# AetherMesh_Test_Fixture_Mezz_V1_0.net
KiCad netlist of a schematic drawn in EAGLE
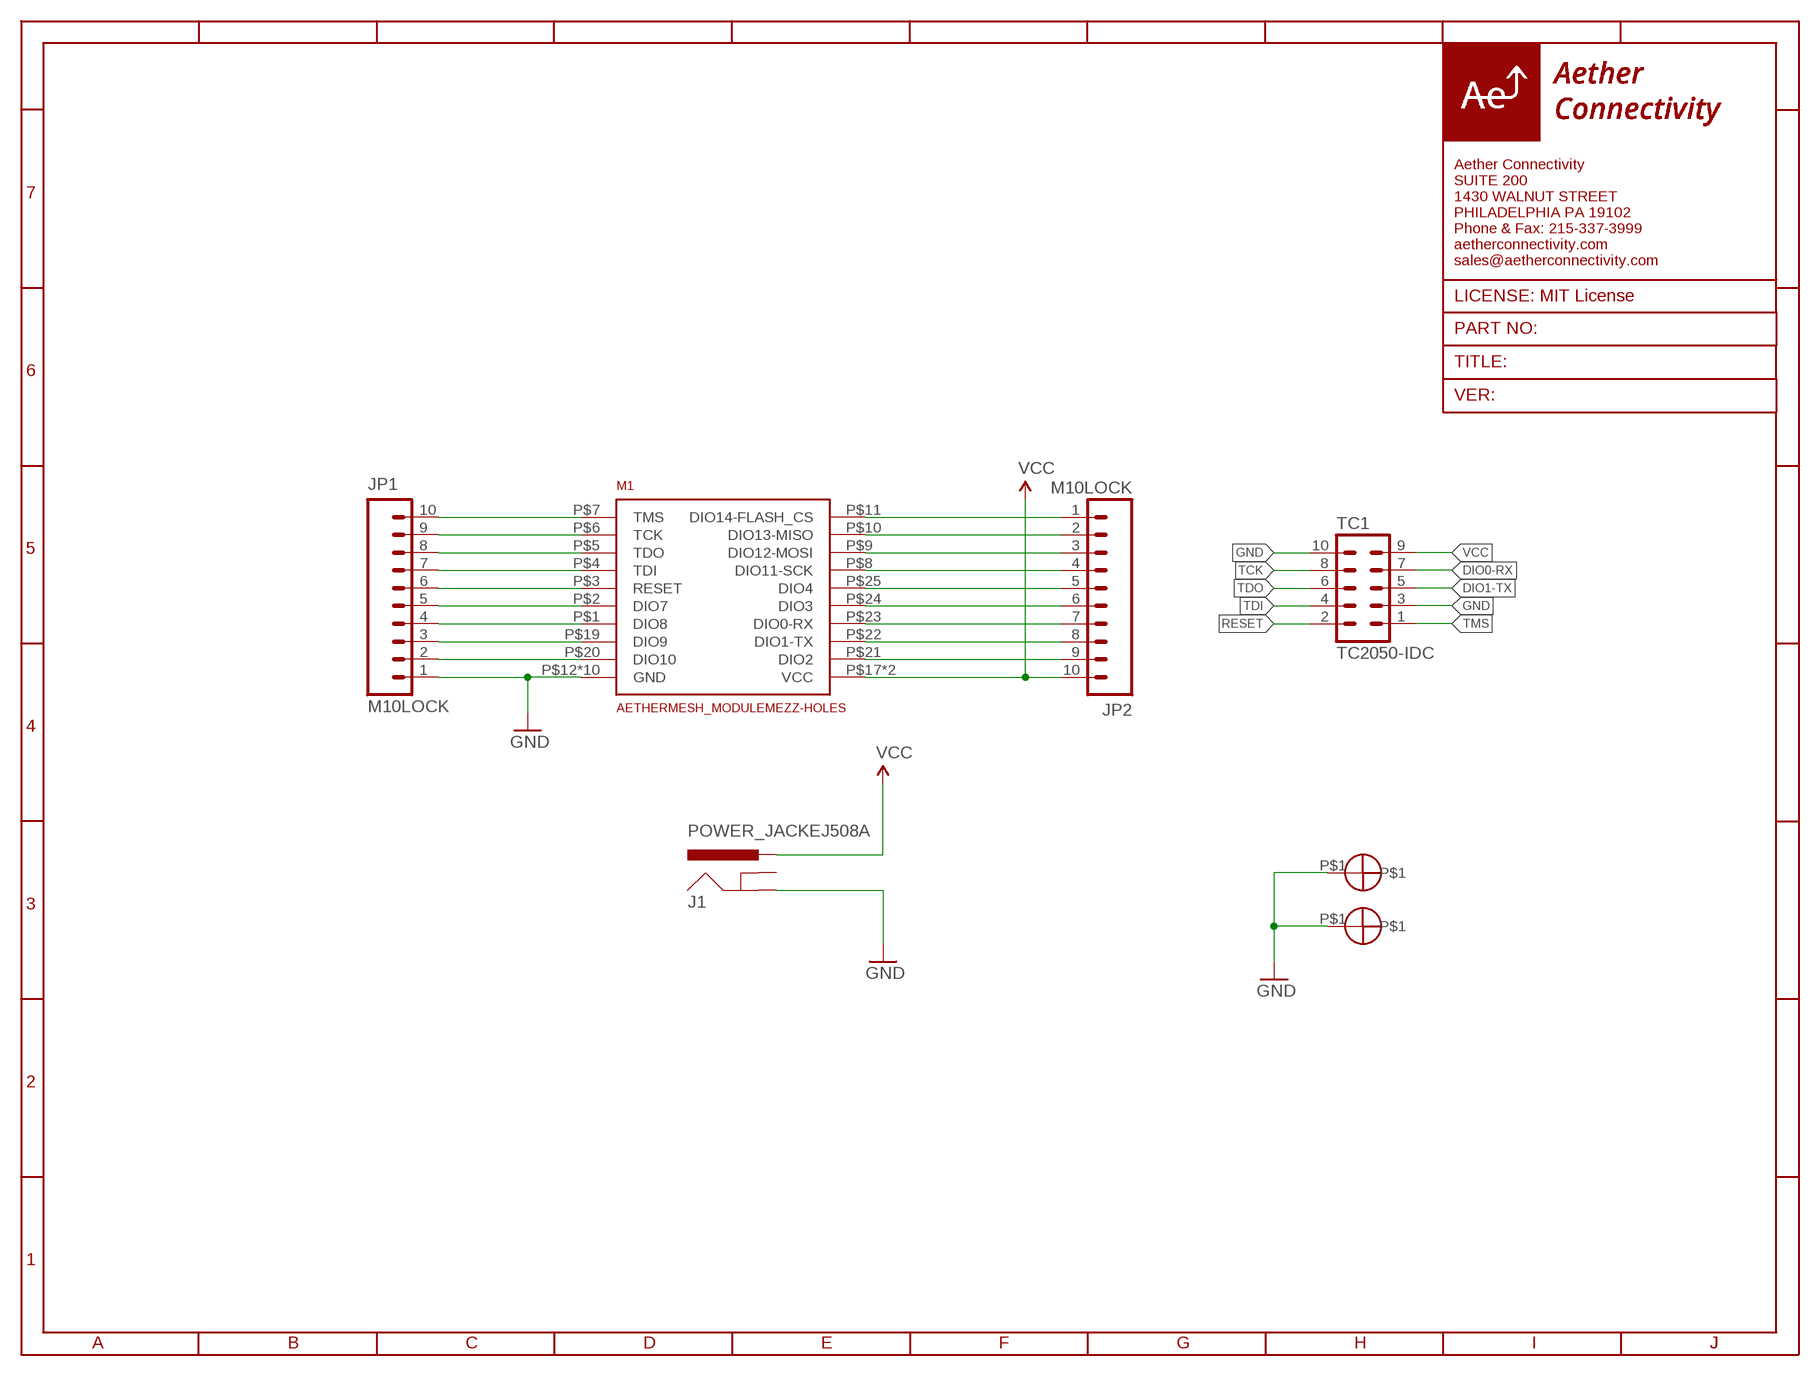
[diagram p0: schematic, sheet 1]

(export (version "E")
  (design (tool "Eeschema 10.0.6"))
  (components
    (comp (ref "J1")
      (value "POWER_JACKEJ508A")
      (footprint "eagle-import:DC_JACK_EJ508A")
      (libsource (lib "eagle-import") (part "POWER_JACKEJ508A"))
    )
    (comp (ref "JP1")
      (value "M10LOCK")
      (footprint "eagle-import:1X10_LOCK")
      (libsource (lib "eagle-import") (part "M10LOCK"))
    )
    (comp (ref "JP2")
      (value "M10LOCK")
      (footprint "eagle-import:1X10_LOCK")
      (libsource (lib "eagle-import") (part "M10LOCK"))
    )
    (comp (ref "M1")
      (value "AETHERMESH_MODULEMEZZ-HOLES")
      (footprint "eagle-import:AETHERMESH_MEZZ_MOUNT_HOLES")
      (libsource (lib "eagle-import") (part "AETHERMESH_MODULEMEZZ-HOLES"))
    )
    (comp (ref "S1")
      (value "STANDOFFWURTH")
      (footprint "eagle-import:STANDOFF_WURTH_9774040243R")
      (libsource (lib "eagle-import") (part "STANDOFFWURTH"))
    )
    (comp (ref "S2")
      (value "STANDOFFWURTH")
      (footprint "eagle-import:STANDOFF_WURTH_9774040243R")
      (libsource (lib "eagle-import") (part "STANDOFFWURTH"))
    )
    (comp (ref "TC1")
      (value "TC2050-IDC")
      (footprint "eagle-import:TC2050-IDC")
      (libsource (lib "eagle-import") (part "TC2050-IDC"))
    )
  )
  (nets
    (net (code "1") (name "DIO0-RX") (class "Default")
      (node (ref "JP2") (pin "7") (pinfunction "7_7") (pintype "passive"))
      (node (ref "M1") (pin "P$23") (pinfunction "DIO0-RX_P$23") (pintype "bidirectional"))
      (node (ref "TC1") (pin "7") (pinfunction "7_7") (pintype "passive"))
    )
    (net (code "2") (name "DIO1-TX") (class "Default")
      (node (ref "JP2") (pin "8") (pinfunction "8_8") (pintype "passive"))
      (node (ref "M1") (pin "P$22") (pinfunction "DIO1-TX_P$22") (pintype "bidirectional"))
      (node (ref "TC1") (pin "5") (pinfunction "5_5") (pintype "passive"))
    )
    (net (code "3") (name "GND") (class "Default")
      (node (ref "J1") (pin "1") (pinfunction "GND_1") (pintype "bidirectional"))
      (node (ref "JP1") (pin "1") (pinfunction "1_1") (pintype "passive"))
      (node (ref "M1") (pin "P$12") (pinfunction "GND_P$12") (pintype "bidirectional"))
      (node (ref "M1") (pin "P$13") (pinfunction "GND_P$13") (pintype "bidirectional"))
      (node (ref "M1") (pin "P$14") (pinfunction "GND_P$14") (pintype "bidirectional"))
      (node (ref "M1") (pin "P$15") (pinfunction "GND_P$15") (pintype "bidirectional"))
      (node (ref "M1") (pin "P$16") (pinfunction "GND_P$16") (pintype "bidirectional"))
      (node (ref "M1") (pin "P$26") (pinfunction "GND_P$26") (pintype "bidirectional"))
      (node (ref "M1") (pin "P$27") (pinfunction "GND_P$27") (pintype "bidirectional"))
      (node (ref "M1") (pin "P$28") (pinfunction "GND_P$28") (pintype "bidirectional"))
      (node (ref "M1") (pin "P$29") (pinfunction "GND_P$29") (pintype "bidirectional"))
      (node (ref "M1") (pin "P$30") (pinfunction "GND_P$30") (pintype "bidirectional"))
      (node (ref "S1") (pin "P$1") (pinfunction "P$1_P$1") (pintype "bidirectional"))
      (node (ref "S2") (pin "P$1") (pinfunction "P$1_P$1") (pintype "bidirectional"))
      (node (ref "TC1") (pin "10") (pinfunction "10_10") (pintype "passive"))
      (node (ref "TC1") (pin "3") (pinfunction "3_3") (pintype "passive"))
    )
    (net (code "4") (name "Net-(M1-DIO2)") (class "Default")
      (node (ref "JP2") (pin "9") (pinfunction "9_9") (pintype "passive"))
      (node (ref "M1") (pin "P$21") (pinfunction "DIO2_P$21") (pintype "bidirectional"))
    )
    (net (code "5") (name "Net-(M1-DIO3)") (class "Default")
      (node (ref "JP2") (pin "6") (pinfunction "6_6") (pintype "passive"))
      (node (ref "M1") (pin "P$24") (pinfunction "DIO3_P$24") (pintype "bidirectional"))
    )
    (net (code "6") (name "Net-(M1-DIO4)") (class "Default")
      (node (ref "JP2") (pin "5") (pinfunction "5_5") (pintype "passive"))
      (node (ref "M1") (pin "P$25") (pinfunction "DIO4_P$25") (pintype "bidirectional"))
    )
    (net (code "7") (name "Net-(M1-DIO7)") (class "Default")
      (node (ref "JP1") (pin "5") (pinfunction "5_5") (pintype "passive"))
      (node (ref "M1") (pin "P$2") (pinfunction "DIO7_P$2") (pintype "bidirectional"))
    )
    (net (code "8") (name "Net-(M1-DIO8)") (class "Default")
      (node (ref "JP1") (pin "4") (pinfunction "4_4") (pintype "passive"))
      (node (ref "M1") (pin "P$1") (pinfunction "DIO8_P$1") (pintype "bidirectional"))
    )
    (net (code "9") (name "Net-(M1-DIO9)") (class "Default")
      (node (ref "JP1") (pin "3") (pinfunction "3_3") (pintype "passive"))
      (node (ref "M1") (pin "P$19") (pinfunction "DIO9_P$19") (pintype "bidirectional"))
    )
    (net (code "10") (name "Net-(M1-DIO10)") (class "Default")
      (node (ref "JP1") (pin "2") (pinfunction "2_2") (pintype "passive"))
      (node (ref "M1") (pin "P$20") (pinfunction "DIO10_P$20") (pintype "bidirectional"))
    )
    (net (code "11") (name "Net-(M1-DIO11-SCK)") (class "Default")
      (node (ref "JP2") (pin "4") (pinfunction "4_4") (pintype "passive"))
      (node (ref "M1") (pin "P$8") (pinfunction "DIO11-SCK_P$8") (pintype "bidirectional"))
    )
    (net (code "12") (name "Net-(M1-DIO12-MOSI)") (class "Default")
      (node (ref "JP2") (pin "3") (pinfunction "3_3") (pintype "passive"))
      (node (ref "M1") (pin "P$9") (pinfunction "DIO12-MOSI_P$9") (pintype "bidirectional"))
    )
    (net (code "13") (name "Net-(M1-DIO13-MISO)") (class "Default")
      (node (ref "JP2") (pin "2") (pinfunction "2_2") (pintype "passive"))
      (node (ref "M1") (pin "P$10") (pinfunction "DIO13-MISO_P$10") (pintype "bidirectional"))
    )
    (net (code "14") (name "Net-(M1-DIO14-FLASH_CS)") (class "Default")
      (node (ref "JP2") (pin "1") (pinfunction "1_1") (pintype "passive"))
      (node (ref "M1") (pin "P$11") (pinfunction "DIO14-FLASH_CS_P$11") (pintype "bidirectional"))
    )
    (net (code "15") (name "RESET") (class "Default")
      (node (ref "JP1") (pin "6") (pinfunction "6_6") (pintype "passive"))
      (node (ref "M1") (pin "P$3") (pinfunction "RESET_P$3") (pintype "bidirectional"))
      (node (ref "TC1") (pin "2") (pinfunction "2_2") (pintype "passive"))
    )
    (net (code "16") (name "TCK") (class "Default")
      (node (ref "JP1") (pin "9") (pinfunction "9_9") (pintype "passive"))
      (node (ref "M1") (pin "P$6") (pinfunction "TCK_P$6") (pintype "bidirectional"))
      (node (ref "TC1") (pin "8") (pinfunction "8_8") (pintype "passive"))
    )
    (net (code "17") (name "TDI") (class "Default")
      (node (ref "JP1") (pin "7") (pinfunction "7_7") (pintype "passive"))
      (node (ref "M1") (pin "P$4") (pinfunction "TDI_P$4") (pintype "bidirectional"))
      (node (ref "TC1") (pin "4") (pinfunction "4_4") (pintype "passive"))
    )
    (net (code "18") (name "TDO") (class "Default")
      (node (ref "JP1") (pin "8") (pinfunction "8_8") (pintype "passive"))
      (node (ref "M1") (pin "P$5") (pinfunction "TDO_P$5") (pintype "bidirectional"))
      (node (ref "TC1") (pin "6") (pinfunction "6_6") (pintype "passive"))
    )
    (net (code "19") (name "TMS") (class "Default")
      (node (ref "JP1") (pin "10") (pinfunction "10_10") (pintype "passive"))
      (node (ref "M1") (pin "P$7") (pinfunction "TMS_P$7") (pintype "bidirectional"))
      (node (ref "TC1") (pin "1") (pinfunction "1_1") (pintype "passive"))
    )
    (net (code "20") (name "VCC") (class "Default")
      (node (ref "J1") (pin "3") (pinfunction "PWR_3") (pintype "bidirectional"))
      (node (ref "JP2") (pin "10") (pinfunction "10_10") (pintype "passive"))
      (node (ref "M1") (pin "P$17") (pinfunction "VCC_P$17") (pintype "bidirectional"))
      (node (ref "M1") (pin "P$18") (pinfunction "VCC_P$18") (pintype "bidirectional"))
      (node (ref "TC1") (pin "9") (pinfunction "9_9") (pintype "passive"))
    )
    (net (code "21") (name "unconnected-(J1-GNDBREAK-Pad2)") (class "Default")
      (node (ref "J1") (pin "2") (pinfunction "GNDBREAK_2") (pintype "bidirectional"))
    )
  )
)
